# sfp-breakout.net
KiCad netlist of a schematic drawn in EAGLE
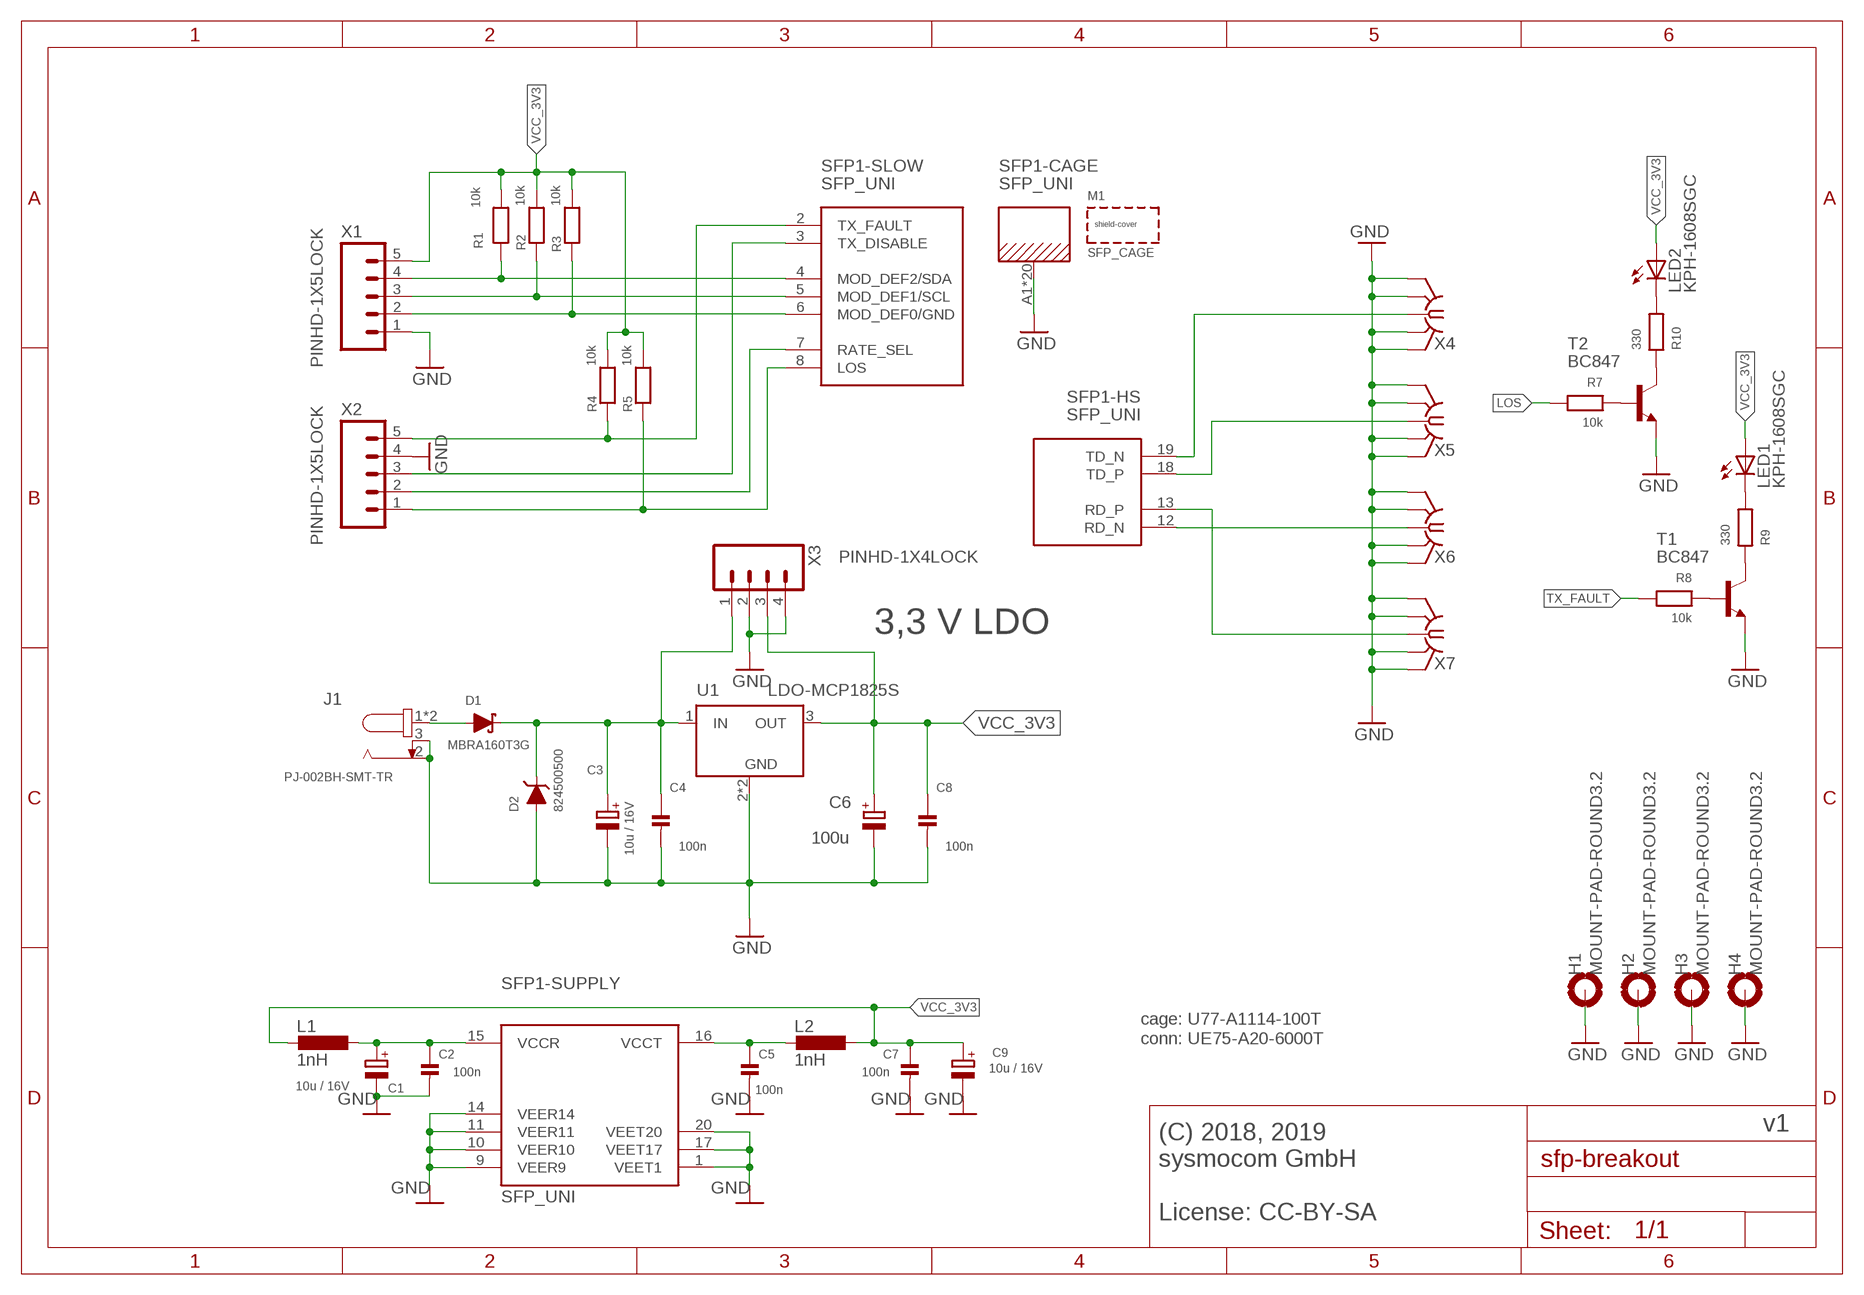
[diagram p0: schematic, sheet 1]

(export (version "E")
  (design (tool "Eeschema 10.0.6"))
  (components
    (comp (ref "C1")
      (value "10u / 16V")
      (footprint "eagle-import:CPOL1206")
      (description "CAP CER 10UF 16V X5R 1206")
      (fields
        (field (name "MANUFACTURER") "Samsung Electro-Mechanics")
        (field (name "MANUFACTURERPARTNUMBER") "CL31A106KOHNNNE")
      )
      (libsource (lib "eagle-import") (part "CPOL-EU-1206"))
    )
    (comp (ref "C2")
      (value "100n")
      (footprint "eagle-import:_0603")
      (description "CAP CER 0.1UF 16V X7R 0603")
      (fields
        (field (name "MANUFACTURER") "Samsung Electro-Mechanics")
        (field (name "MANUFACTURERPARTNUMBER") "CL10B104KO8NNNC")
      )
      (libsource (lib "eagle-import") (part "CAP_CERAMIC_0603"))
    )
    (comp (ref "C3")
      (value "10u / 16V")
      (footprint "eagle-import:CPOL1206")
      (description "CAP CER 10UF 16V X5R 1206")
      (fields
        (field (name "MANUFACTURER") "Samsung Electro-Mechanics")
        (field (name "MANUFACTURERPARTNUMBER") "CL31A106KOHNNNE")
      )
      (libsource (lib "eagle-import") (part "CPOL-EU-1206"))
    )
    (comp (ref "C4")
      (value "100n")
      (footprint "eagle-import:_0603")
      (description "CAP CER 0.1UF 16V X7R 0603")
      (fields
        (field (name "MANUFACTURER") "Samsung Electro-Mechanics")
        (field (name "MANUFACTURERPARTNUMBER") "CL10B104KO8NNNC")
      )
      (libsource (lib "eagle-import") (part "CAP_CERAMIC_0603"))
    )
    (comp (ref "C5")
      (value "100n")
      (footprint "eagle-import:_0603")
      (description "CAP CER 0.1UF 16V X7R 0603")
      (fields
        (field (name "MANUFACTURER") "Samsung Electro-Mechanics")
        (field (name "MANUFACTURERPARTNUMBER") "CL10B104KO8NNNC")
      )
      (libsource (lib "eagle-import") (part "CAP_CERAMIC_0603"))
    )
    (comp (ref "C6")
      (value "100u")
      (footprint "eagle-import:CT6032")
      (description "CAP TANT 100UF 10% 6.3V 2312")
      (fields
        (field (name "MANUFACTURER") "AVX Corporation")
        (field (name "MANUFACTURERPARTNUMBER") "TPSC107K006R0150")
      )
      (libsource (lib "eagle-import") (part "CPOL-EUCT6032"))
    )
    (comp (ref "C7")
      (value "100n")
      (footprint "eagle-import:_0603")
      (description "CAP CER 0.1UF 16V X7R 0603")
      (fields
        (field (name "MANUFACTURER") "Samsung Electro-Mechanics")
        (field (name "MANUFACTURERPARTNUMBER") "CL10B104KO8NNNC")
      )
      (libsource (lib "eagle-import") (part "CAP_CERAMIC_0603"))
    )
    (comp (ref "C8")
      (value "100n")
      (footprint "eagle-import:_0603")
      (description "CAP CER 0.1UF 16V X7R 0603")
      (fields
        (field (name "MANUFACTURER") "Samsung Electro-Mechanics")
        (field (name "MANUFACTURERPARTNUMBER") "CL10B104KO8NNNC")
      )
      (libsource (lib "eagle-import") (part "CAP_CERAMIC_0603"))
    )
    (comp (ref "C9")
      (value "10u / 16V")
      (footprint "eagle-import:CPOL1206")
      (description "CAP CER 10UF 16V X5R 1206")
      (fields
        (field (name "MANUFACTURER") "Samsung Electro-Mechanics")
        (field (name "MANUFACTURERPARTNUMBER") "CL31A106KOHNNNE")
      )
      (libsource (lib "eagle-import") (part "CPOL-EU-1206"))
    )
    (comp (ref "D1")
      (value "MBRA160T3G")
      (footprint "eagle-import:SMADIODE")
      (description "DIODE SCHOTTKY 60V 2A SMA")
      (fields
        (field (name "MANUFACTURER") "Diodes Incorporated")
        (field (name "MANUFACTURERPARTNUMBER") "B260A-13-F")
      )
      (libsource (lib "eagle-import") (part "DIODE-SCHOTTKY-SMA"))
    )
    (comp (ref "D2")
      (value "824500500")
      (footprint "eagle-import:SMADIODE")
      (description "TVS DIODE 5V 9.2V DO214AC")
      (fields (field (name "MANUFACTURER") "Würth Elektronik"))
      (libsource (lib "eagle-import") (part "DIODE-TVS-SMA"))
    )
    (comp (ref "H1")
      (value "MOUNT-PAD-ROUND3.2")
      (footprint "eagle-import:3,2-PAD")
      (description "NO DESCRIPTION")
      (fields
        (field (name "MANUFACTURER") "UNKNOWN MANUFACTURER")
        (field (name "MANUFACTURERPARTNUMBER") "UNKNOWN MANUFACTURER PART NUMBER")
      )
      (libsource (lib "eagle-import") (part "MOUNT-PAD-ROUND3.2"))
    )
    (comp (ref "H2")
      (value "MOUNT-PAD-ROUND3.2")
      (footprint "eagle-import:3,2-PAD")
      (description "NO DESCRIPTION")
      (fields
        (field (name "MANUFACTURER") "UNKNOWN MANUFACTURER")
        (field (name "MANUFACTURERPARTNUMBER") "UNKNOWN MANUFACTURER PART NUMBER")
      )
      (libsource (lib "eagle-import") (part "MOUNT-PAD-ROUND3.2"))
    )
    (comp (ref "H3")
      (value "MOUNT-PAD-ROUND3.2")
      (footprint "eagle-import:3,2-PAD")
      (description "NO DESCRIPTION")
      (fields
        (field (name "MANUFACTURER") "UNKNOWN MANUFACTURER")
        (field (name "MANUFACTURERPARTNUMBER") "UNKNOWN MANUFACTURER PART NUMBER")
      )
      (libsource (lib "eagle-import") (part "MOUNT-PAD-ROUND3.2"))
    )
    (comp (ref "H4")
      (value "MOUNT-PAD-ROUND3.2")
      (footprint "eagle-import:3,2-PAD")
      (description "NO DESCRIPTION")
      (fields
        (field (name "MANUFACTURER") "UNKNOWN MANUFACTURER")
        (field (name "MANUFACTURERPARTNUMBER") "UNKNOWN MANUFACTURER PART NUMBER")
      )
      (libsource (lib "eagle-import") (part "MOUNT-PAD-ROUND3.2"))
    )
    (comp (ref "J1")
      (value "PJ-002BH-SMT-TR")
      (footprint "eagle-import:694108106102")
      (description "CONN PWR JACK 2.5X5.5MM SOLDER")
      (fields (field (name "MANUFACTURER") "CUI Devices"))
      (libsource (lib "eagle-import") (part "694108106102"))
    )
    (comp (ref "L1")
      (value "1nH")
      (footprint "eagle-import:0603")
      (description "FIXED IND 1NH 500MA 50 MOHM SMD")
      (fields
        (field (name "MANUFACTURER") "Abracon LLC")
        (field (name "MANUFACTURERPARTNUMBER") "AIMC-0603-1N0S-T")
      )
      (libsource (lib "eagle-import") (part "L-EU_0603"))
    )
    (comp (ref "L2")
      (value "1nH")
      (footprint "eagle-import:0603")
      (description "FIXED IND 1NH 500MA 50 MOHM SMD")
      (fields
        (field (name "MANUFACTURER") "Abracon LLC")
        (field (name "MANUFACTURERPARTNUMBER") "AIMC-0603-1N0S-T")
      )
      (libsource (lib "eagle-import") (part "L-EU_0603"))
    )
    (comp (ref "LED1")
      (value "KPH-1608SGC")
      (footprint "eagle-import:CHIP-LED0603")
      (description "NO DESCRIPTION")
      (fields
        (field (name "MANUFACTURER") "UNKNOWN MANUFACTURER")
        (field (name "MANUFACTURERPARTNUMBER") "UNKNOWN MANUFACTURER PART NUMBER")
      )
      (libsource (lib "eagle-import") (part "LEDCHIP-LED0603"))
    )
    (comp (ref "LED2")
      (value "KPH-1608SGC")
      (footprint "eagle-import:CHIP-LED0603")
      (description "NO DESCRIPTION")
      (fields
        (field (name "MANUFACTURER") "UNKNOWN MANUFACTURER")
        (field (name "MANUFACTURERPARTNUMBER") "UNKNOWN MANUFACTURER PART NUMBER")
      )
      (libsource (lib "eagle-import") (part "LEDCHIP-LED0603"))
    )
    (comp (ref "R1")
      (value "10k")
      (footprint "eagle-import:_0603")
      (description "RES 10K OHM 1% 1/10W 0603")
      (fields
        (field (name "MANUFACTURER") "Stackpole Electronics Inc")
        (field (name "MANUFACTURERPARTNUMBER") "RMCF0603FT10K0")
      )
      (libsource (lib "eagle-import") (part "sfp-breakout_RESISTOR_0603"))
    )
    (comp (ref "R2")
      (value "10k")
      (footprint "eagle-import:_0603")
      (description "RES 10K OHM 1% 1/10W 0603")
      (fields
        (field (name "MANUFACTURER") "Stackpole Electronics Inc")
        (field (name "MANUFACTURERPARTNUMBER") "RMCF0603FT10K0")
      )
      (libsource (lib "eagle-import") (part "sfp-breakout_RESISTOR_0603"))
    )
    (comp (ref "R3")
      (value "10k")
      (footprint "eagle-import:_0603")
      (description "RES 10K OHM 1% 1/10W 0603")
      (fields
        (field (name "MANUFACTURER") "Stackpole Electronics Inc")
        (field (name "MANUFACTURERPARTNUMBER") "RMCF0603FT10K0")
      )
      (libsource (lib "eagle-import") (part "sfp-breakout_RESISTOR_0603"))
    )
    (comp (ref "R4")
      (value "10k")
      (footprint "eagle-import:_0603")
      (description "RES 10K OHM 1% 1/10W 0603")
      (fields
        (field (name "MANUFACTURER") "Stackpole Electronics Inc")
        (field (name "MANUFACTURERPARTNUMBER") "RMCF0603FT10K0")
      )
      (libsource (lib "eagle-import") (part "sfp-breakout_RESISTOR_0603"))
    )
    (comp (ref "R5")
      (value "10k")
      (footprint "eagle-import:_0603")
      (description "RES 10K OHM 1% 1/10W 0603")
      (fields
        (field (name "MANUFACTURER") "Stackpole Electronics Inc")
        (field (name "MANUFACTURERPARTNUMBER") "RMCF0603FT10K0")
      )
      (libsource (lib "eagle-import") (part "sfp-breakout_RESISTOR_0603"))
    )
    (comp (ref "R7")
      (value "10k")
      (footprint "eagle-import:_0603")
      (description "RES 10K OHM 1% 1/10W 0603")
      (fields
        (field (name "MANUFACTURER") "Stackpole Electronics Inc")
        (field (name "MANUFACTURERPARTNUMBER") "RMCF0603FT10K0")
      )
      (libsource (lib "eagle-import") (part "RESISTOR_0603"))
    )
    (comp (ref "R8")
      (value "10k")
      (footprint "eagle-import:_0603")
      (description "RES 10K OHM 1% 1/10W 0603")
      (fields
        (field (name "MANUFACTURER") "Stackpole Electronics Inc")
        (field (name "MANUFACTURERPARTNUMBER") "RMCF0603FT10K0")
      )
      (libsource (lib "eagle-import") (part "RESISTOR_0603"))
    )
    (comp (ref "R9")
      (value "330")
      (footprint "eagle-import:_0603")
      (description "RES SMD 330 OHM 1% 1/10W 0603")
      (fields
        (field (name "MANUFACTURER") "Yageo")
        (field (name "MANUFACTURERPARTNUMBER") "RC0603FR-07330RL")
      )
      (libsource (lib "eagle-import") (part "RESISTOR_0603"))
    )
    (comp (ref "R10")
      (value "330")
      (footprint "eagle-import:_0603")
      (description "RES SMD 330 OHM 1% 1/10W 0603")
      (fields
        (field (name "MANUFACTURER") "Yageo")
        (field (name "MANUFACTURERPARTNUMBER") "RC0603FR-07330RL")
      )
      (libsource (lib "eagle-import") (part "RESISTOR_0603"))
    )
    (comp (ref "SFP1")
      (value "SFP_UNI")
      (footprint "eagle-import:SFP_COMBINED")
      (description "CONN SFP RCPT 20POS SLD R/A SMD")
      (fields
        (field (name "CLASS") "CONNECTOR")
        (field (name "LINK") "https://www.digikey.com/product-detail/en/amphenol-icc-commercial-products/UE75-A20-6000T/UE75-A20-6000TCT-ND/1242798")
        (field (name "MANUFACTURER") "Amphenol ICC (Commercial Products)")
        (field (name "MANUFACTURERPARTNUMBER") "UE75-A20-6000T")
        (field (name "POPULATED") "TRUE")
        (field (name "ROHSCERTIFICATE") "RoHS Compliant")
        (field (name "SOURCE") "DIGIKEY")
        (field (name "SOURCEPARTNUMBER") "UE75-A20-6000TCT-ND")
      )
      (libsource (lib "eagle-import") (part "SFP_UNI"))
    )
    (comp (ref "T1")
      (value "BC847")
      (footprint "eagle-import:SOT23-BEC")
      (description "TRANS NPN 45V 0.1A SOT23")
      (fields
        (field (name "MANUFACTURER") "Nexperia USA Inc.")
        (field (name "MANUFACTURERPARTNUMBER") "BC847C,215")
      )
      (libsource (lib "eagle-import") (part "-NPN-SOT23-BECBC847C"))
    )
    (comp (ref "T2")
      (value "BC847")
      (footprint "eagle-import:SOT23-BEC")
      (description "TRANS NPN 45V 0.1A SOT23")
      (fields
        (field (name "MANUFACTURER") "Nexperia USA Inc.")
        (field (name "MANUFACTURERPARTNUMBER") "BC847C,215")
      )
      (libsource (lib "eagle-import") (part "-NPN-SOT23-BECBC847C"))
    )
    (comp (ref "U1")
      (value "LDO-MCP1825S")
      (footprint "eagle-import:SOT223")
      (description "IC REG LIN 3.3V 500MA SOT223-3")
      (fields
        (field (name "MANUFACTURER") "Microchip Technology")
        (field (name "MANUFACTURERPARTNUMBER") "MCP1825ST-3302E/DB")
      )
      (libsource (lib "eagle-import") (part "LDO-MCP1825S"))
    )
    (comp (ref "X1")
      (value "PINHD-1X5LOCK")
      (footprint "eagle-import:1X05_LOCK")
      (description "NO DESCRIPTION")
      (fields
        (field (name "MANUFACTURER") "UNKNOWN MANUFACTURER")
        (field (name "MANUFACTURERPARTNUMBER") "UNKNOWN MANUFACTURER PART NUMBER")
      )
      (libsource (lib "eagle-import") (part "PINHD-1X5LOCK"))
    )
    (comp (ref "X2")
      (value "PINHD-1X5LOCK")
      (footprint "eagle-import:1X05_LOCK")
      (description "NO DESCRIPTION")
      (fields
        (field (name "MANUFACTURER") "UNKNOWN MANUFACTURER")
        (field (name "MANUFACTURERPARTNUMBER") "UNKNOWN MANUFACTURER PART NUMBER")
      )
      (libsource (lib "eagle-import") (part "PINHD-1X5LOCK"))
    )
    (comp (ref "X3")
      (value "PINHD-1X4LOCK")
      (footprint "eagle-import:1X04_LOCK")
      (description "NO DESCRIPTION")
      (fields
        (field (name "MANUFACTURER") "UNKNOWN MANUFACTURER")
        (field (name "MANUFACTURERPARTNUMBER") "UNKNOWN MANUFACTURER PART NUMBER")
      )
      (libsource (lib "eagle-import") (part "PINHD-1X4LOCK"))
    )
    (comp (ref "X4")
      (value "SMA-F-S-EDGE")
      (footprint "eagle-import:SMA-F-S-EDGE")
      (description "NO DESCRIPTION")
      (fields
        (field (name "MANUFACTURER") "UNKNOWN MANUFACTURER")
        (field (name "MANUFACTURERPARTNUMBER") "UNKNOWN MANUFACTURER PART NUMBER")
      )
      (libsource (lib "eagle-import") (part "SMA-F-S-EDGE"))
    )
    (comp (ref "X5")
      (value "SMA-F-S-EDGE")
      (footprint "eagle-import:SMA-F-S-EDGE")
      (description "NO DESCRIPTION")
      (fields
        (field (name "MANUFACTURER") "UNKNOWN MANUFACTURER")
        (field (name "MANUFACTURERPARTNUMBER") "UNKNOWN MANUFACTURER PART NUMBER")
      )
      (libsource (lib "eagle-import") (part "SMA-F-S-EDGE"))
    )
    (comp (ref "X6")
      (value "SMA-F-S-EDGE")
      (footprint "eagle-import:SMA-F-S-EDGE")
      (description "NO DESCRIPTION")
      (fields
        (field (name "MANUFACTURER") "UNKNOWN MANUFACTURER")
        (field (name "MANUFACTURERPARTNUMBER") "UNKNOWN MANUFACTURER PART NUMBER")
      )
      (libsource (lib "eagle-import") (part "SMA-F-S-EDGE"))
    )
    (comp (ref "X7")
      (value "SMA-F-S-EDGE")
      (footprint "eagle-import:SMA-F-S-EDGE")
      (description "NO DESCRIPTION")
      (fields
        (field (name "MANUFACTURER") "UNKNOWN MANUFACTURER")
        (field (name "MANUFACTURERPARTNUMBER") "UNKNOWN MANUFACTURER PART NUMBER")
      )
      (libsource (lib "eagle-import") (part "SMA-F-S-EDGE"))
    )
  )
  (nets
    (net (code "1") (name "GND") (class "Default")
      (node (ref "C1") (pin "-") (pinfunction "-_-") (pintype "passive"))
      (node (ref "C2") (pin "2") (pinfunction "2_2") (pintype "passive"))
      (node (ref "C3") (pin "-") (pinfunction "-_-") (pintype "passive"))
      (node (ref "C4") (pin "2") (pinfunction "2_2") (pintype "passive"))
      (node (ref "C5") (pin "2") (pinfunction "2_2") (pintype "passive"))
      (node (ref "C6") (pin "-") (pinfunction "-_-") (pintype "passive"))
      (node (ref "C7") (pin "2") (pinfunction "2_2") (pintype "passive"))
      (node (ref "C8") (pin "2") (pinfunction "2_2") (pintype "passive"))
      (node (ref "C9") (pin "-") (pinfunction "-_-") (pintype "passive"))
      (node (ref "D2") (pin "A") (pinfunction "A_A") (pintype "passive"))
      (node (ref "H1") (pin "B3,2") (pinfunction "MOUNT_B3,2") (pintype "passive"))
      (node (ref "H2") (pin "B3,2") (pinfunction "MOUNT_B3,2") (pintype "passive"))
      (node (ref "H3") (pin "B3,2") (pinfunction "MOUNT_B3,2") (pintype "passive"))
      (node (ref "H4") (pin "B3,2") (pinfunction "MOUNT_B3,2") (pintype "passive"))
      (node (ref "J1") (pin "2") (pinfunction "2_2") (pintype "passive"))
      (node (ref "J1") (pin "3") (pinfunction "3_3") (pintype "passive"))
      (node (ref "SFP1") (pin "1") (pinfunction "VEET1_1") (pintype "power_in"))
      (node (ref "SFP1") (pin "10") (pinfunction "VEER10_10") (pintype "power_in"))
      (node (ref "SFP1") (pin "11") (pinfunction "VEER11_11") (pintype "power_in"))
      (node (ref "SFP1") (pin "14") (pinfunction "VEER14_14") (pintype "power_in"))
      (node (ref "SFP1") (pin "17") (pinfunction "VEET17_17") (pintype "power_in"))
      (node (ref "SFP1") (pin "20") (pinfunction "VEET20_20") (pintype "power_in"))
      (node (ref "SFP1") (pin "9") (pinfunction "VEER9_9") (pintype "power_in"))
      (node (ref "SFP1") (pin "A1") (pinfunction "CAGE_A1") (pintype "power_in"))
      (node (ref "SFP1") (pin "A10") (pinfunction "CAGE_A10") (pintype "power_in"))
      (node (ref "SFP1") (pin "A11") (pinfunction "CAGE_A11") (pintype "power_in"))
      (node (ref "SFP1") (pin "A12") (pinfunction "CAGE_A12") (pintype "power_in"))
      (node (ref "SFP1") (pin "A2") (pinfunction "CAGE_A2") (pintype "power_in"))
      (node (ref "SFP1") (pin "A3") (pinfunction "CAGE_A3") (pintype "power_in"))
      (node (ref "SFP1") (pin "A4") (pinfunction "CAGE_A4") (pintype "power_in"))
      (node (ref "SFP1") (pin "A5") (pinfunction "CAGE_A5") (pintype "power_in"))
      (node (ref "SFP1") (pin "A6") (pinfunction "CAGE_A6") (pintype "power_in"))
      (node (ref "SFP1") (pin "A7") (pinfunction "CAGE_A7") (pintype "power_in"))
      (node (ref "SFP1") (pin "A8") (pinfunction "CAGE_A8") (pintype "power_in"))
      (node (ref "SFP1") (pin "B1") (pinfunction "CAGE_B1") (pintype "power_in"))
      (node (ref "SFP1") (pin "B10") (pinfunction "CAGE_B10") (pintype "power_in"))
      (node (ref "SFP1") (pin "B2") (pinfunction "CAGE_B2") (pintype "power_in"))
      (node (ref "SFP1") (pin "B3") (pinfunction "CAGE_B3") (pintype "power_in"))
      (node (ref "SFP1") (pin "B4") (pinfunction "CAGE_B4") (pintype "power_in"))
      (node (ref "SFP1") (pin "B5") (pinfunction "CAGE_B5") (pintype "power_in"))
      (node (ref "SFP1") (pin "B6") (pinfunction "CAGE_B6") (pintype "power_in"))
      (node (ref "SFP1") (pin "B7") (pinfunction "CAGE_B7") (pintype "power_in"))
      (node (ref "SFP1") (pin "B8") (pinfunction "CAGE_B8") (pintype "power_in"))
      (node (ref "T1") (pin "E") (pinfunction "E_E") (pintype "passive"))
      (node (ref "T2") (pin "E") (pinfunction "E_E") (pintype "passive"))
      (node (ref "U1") (pin "2") (pinfunction "GND_2") (pintype "power_in"))
      (node (ref "U1") (pin "4") (pinfunction "GND_4") (pintype "power_in"))
      (node (ref "X1") (pin "1") (pinfunction "1_1") (pintype "passive"))
      (node (ref "X2") (pin "4") (pinfunction "4_4") (pintype "passive"))
      (node (ref "X3") (pin "2") (pinfunction "2_2") (pintype "passive"))
      (node (ref "X3") (pin "4") (pinfunction "4_4") (pintype "passive"))
      (node (ref "X4") (pin "BG1") (pinfunction "GND_BG1") (pintype "power_in"))
      (node (ref "X4") (pin "BG2") (pinfunction "GND_BG2") (pintype "power_in"))
      (node (ref "X4") (pin "TG1") (pinfunction "GND_TG1") (pintype "power_in"))
      (node (ref "X4") (pin "TG2") (pinfunction "GND_TG2") (pintype "power_in"))
      (node (ref "X5") (pin "BG1") (pinfunction "GND_BG1") (pintype "power_in"))
      (node (ref "X5") (pin "BG2") (pinfunction "GND_BG2") (pintype "power_in"))
      (node (ref "X5") (pin "TG1") (pinfunction "GND_TG1") (pintype "power_in"))
      (node (ref "X5") (pin "TG2") (pinfunction "GND_TG2") (pintype "power_in"))
      (node (ref "X6") (pin "BG1") (pinfunction "GND_BG1") (pintype "power_in"))
      (node (ref "X6") (pin "BG2") (pinfunction "GND_BG2") (pintype "power_in"))
      (node (ref "X6") (pin "TG1") (pinfunction "GND_TG1") (pintype "power_in"))
      (node (ref "X6") (pin "TG2") (pinfunction "GND_TG2") (pintype "power_in"))
      (node (ref "X7") (pin "BG1") (pinfunction "GND_BG1") (pintype "power_in"))
      (node (ref "X7") (pin "BG2") (pinfunction "GND_BG2") (pintype "power_in"))
      (node (ref "X7") (pin "TG1") (pinfunction "GND_TG1") (pintype "power_in"))
      (node (ref "X7") (pin "TG2") (pinfunction "GND_TG2") (pintype "power_in"))
    )
    (net (code "2") (name "LOS") (class "Default")
      (node (ref "R5") (pin "1") (pinfunction "1_1") (pintype "passive"))
      (node (ref "R7") (pin "2") (pinfunction "2_2") (pintype "passive"))
      (node (ref "SFP1") (pin "8") (pinfunction "LOS_8") (pintype "output"))
      (node (ref "X2") (pin "1") (pinfunction "1_1") (pintype "passive"))
    )
    (net (code "3") (name "Net-(D1-PadA)") (class "Default")
      (node (ref "D1") (pin "A") (pinfunction "A_A") (pintype "passive"))
      (node (ref "J1") (pin "1") (pinfunction "1_1") (pintype "passive"))
      (node (ref "J1") (pin "1-1") (pinfunction "1_1-1") (pintype "passive"))
    )
    (net (code "4") (name "Net-(LED1-PadC)") (class "Default")
      (node (ref "LED1") (pin "C") (pinfunction "C_C") (pintype "passive"))
      (node (ref "R9") (pin "2") (pinfunction "2_2") (pintype "passive"))
    )
    (net (code "5") (name "Net-(LED2-PadC)") (class "Default")
      (node (ref "LED2") (pin "C") (pinfunction "C_C") (pintype "passive"))
      (node (ref "R10") (pin "2") (pinfunction "2_2") (pintype "passive"))
    )
    (net (code "6") (name "Net-(R7-Pad1)") (class "Default")
      (node (ref "R7") (pin "1") (pinfunction "1_1") (pintype "passive"))
      (node (ref "T2") (pin "B") (pinfunction "B_B") (pintype "passive"))
    )
    (net (code "7") (name "Net-(R8-Pad1)") (class "Default")
      (node (ref "R8") (pin "1") (pinfunction "1_1") (pintype "passive"))
      (node (ref "T1") (pin "B") (pinfunction "B_B") (pintype "passive"))
    )
    (net (code "8") (name "Net-(R9-Pad1)") (class "Default")
      (node (ref "R9") (pin "1") (pinfunction "1_1") (pintype "passive"))
      (node (ref "T1") (pin "C") (pinfunction "C_C") (pintype "passive"))
    )
    (net (code "9") (name "Net-(R10-Pad1)") (class "Default")
      (node (ref "R10") (pin "1") (pinfunction "1_1") (pintype "passive"))
      (node (ref "T2") (pin "C") (pinfunction "C_C") (pintype "passive"))
    )
    (net (code "10") (name "Net-(SFP1B-RD_N)") (class "Default")
      (node (ref "SFP1") (pin "12") (pinfunction "RD_N_12") (pintype "output"))
      (node (ref "X6") (pin "C") (pinfunction "1_C") (pintype "passive"))
    )
    (net (code "11") (name "Net-(SFP1B-RD_P)") (class "Default")
      (node (ref "SFP1") (pin "13") (pinfunction "RD_P_13") (pintype "output"))
      (node (ref "X7") (pin "C") (pinfunction "1_C") (pintype "passive"))
    )
    (net (code "12") (name "Net-(SFP1B-TD_N)") (class "Default")
      (node (ref "SFP1") (pin "19") (pinfunction "TD_N_19") (pintype "input"))
      (node (ref "X4") (pin "C") (pinfunction "1_C") (pintype "passive"))
    )
    (net (code "13") (name "Net-(SFP1B-TD_P)") (class "Default")
      (node (ref "SFP1") (pin "18") (pinfunction "TD_P_18") (pintype "input"))
      (node (ref "X5") (pin "C") (pinfunction "1_C") (pintype "passive"))
    )
    (net (code "14") (name "Net-(SFP1C-MOD_DEF0{slash}GND)") (class "Default")
      (node (ref "R3") (pin "1") (pinfunction "1_1") (pintype "passive"))
      (node (ref "SFP1") (pin "6") (pinfunction "MOD_DEF0/GND_6") (pintype "passive"))
      (node (ref "X1") (pin "2") (pinfunction "2_2") (pintype "passive"))
    )
    (net (code "15") (name "Net-(SFP1C-MOD_DEF1{slash}SCL)") (class "Default")
      (node (ref "R2") (pin "1") (pinfunction "1_1") (pintype "passive"))
      (node (ref "SFP1") (pin "5") (pinfunction "MOD_DEF1/SCL_5") (pintype "bidirectional"))
      (node (ref "X1") (pin "3") (pinfunction "3_3") (pintype "passive"))
    )
    (net (code "16") (name "Net-(SFP1C-MOD_DEF2{slash}SDA)") (class "Default")
      (node (ref "R1") (pin "1") (pinfunction "1_1") (pintype "passive"))
      (node (ref "SFP1") (pin "4") (pinfunction "MOD_DEF2/SDA_4") (pintype "bidirectional"))
      (node (ref "X1") (pin "4") (pinfunction "4_4") (pintype "passive"))
    )
    (net (code "17") (name "Net-(SFP1C-RATE_SEL)") (class "Default")
      (node (ref "SFP1") (pin "7") (pinfunction "RATE_SEL_7") (pintype "input"))
      (node (ref "X2") (pin "2") (pinfunction "2_2") (pintype "passive"))
    )
    (net (code "18") (name "Net-(SFP1C-TX_DISABLE)") (class "Default")
      (node (ref "SFP1") (pin "3") (pinfunction "TX_DISABLE_3") (pintype "input"))
      (node (ref "X2") (pin "3") (pinfunction "3_3") (pintype "passive"))
    )
    (net (code "19") (name "Net-(SFP1D-VCCR)") (class "Default")
      (node (ref "C1") (pin "+") (pinfunction "+_+") (pintype "passive"))
      (node (ref "C2") (pin "1") (pinfunction "1_1") (pintype "passive"))
      (node (ref "L1") (pin "1") (pinfunction "1_1") (pintype "passive"))
      (node (ref "SFP1") (pin "15") (pinfunction "VCCR_15") (pintype "power_in"))
    )
    (net (code "20") (name "Net-(SFP1D-VCCT)") (class "Default")
      (node (ref "C5") (pin "1") (pinfunction "1_1") (pintype "passive"))
      (node (ref "L2") (pin "2") (pinfunction "2_2") (pintype "passive"))
      (node (ref "SFP1") (pin "16") (pinfunction "VCCT_16") (pintype "power_in"))
    )
    (net (code "21") (name "Net-(U1-IN)") (class "Default")
      (node (ref "C3") (pin "+") (pinfunction "+_+") (pintype "passive"))
      (node (ref "C4") (pin "1") (pinfunction "1_1") (pintype "passive"))
      (node (ref "D1") (pin "C") (pinfunction "C_C") (pintype "passive"))
      (node (ref "D2") (pin "C") (pinfunction "C_C") (pintype "passive"))
      (node (ref "U1") (pin "1") (pinfunction "IN_1") (pintype "input"))
      (node (ref "X3") (pin "1") (pinfunction "1_1") (pintype "passive"))
    )
    (net (code "22") (name "TX_FAULT") (class "Default")
      (node (ref "R4") (pin "1") (pinfunction "1_1") (pintype "passive"))
      (node (ref "R8") (pin "2") (pinfunction "2_2") (pintype "passive"))
      (node (ref "SFP1") (pin "2") (pinfunction "TX_FAULT_2") (pintype "output"))
      (node (ref "X2") (pin "5") (pinfunction "5_5") (pintype "passive"))
    )
    (net (code "23") (name "VCC_3V3") (class "Default")
      (node (ref "C6") (pin "+") (pinfunction "+_+") (pintype "passive"))
      (node (ref "C7") (pin "1") (pinfunction "1_1") (pintype "passive"))
      (node (ref "C8") (pin "1") (pinfunction "1_1") (pintype "passive"))
      (node (ref "C9") (pin "+") (pinfunction "+_+") (pintype "passive"))
      (node (ref "L1") (pin "2") (pinfunction "2_2") (pintype "passive"))
      (node (ref "L2") (pin "1") (pinfunction "1_1") (pintype "passive"))
      (node (ref "LED1") (pin "A") (pinfunction "A_A") (pintype "passive"))
      (node (ref "LED2") (pin "A") (pinfunction "A_A") (pintype "passive"))
      (node (ref "R1") (pin "2") (pinfunction "2_2") (pintype "passive"))
      (node (ref "R2") (pin "2") (pinfunction "2_2") (pintype "passive"))
      (node (ref "R3") (pin "2") (pinfunction "2_2") (pintype "passive"))
      (node (ref "R4") (pin "2") (pinfunction "2_2") (pintype "passive"))
      (node (ref "R5") (pin "2") (pinfunction "2_2") (pintype "passive"))
      (node (ref "U1") (pin "3") (pinfunction "OUT_3") (pintype "passive"))
      (node (ref "X1") (pin "5") (pinfunction "5_5") (pintype "passive"))
      (node (ref "X3") (pin "3") (pinfunction "3_3") (pintype "passive"))
    )
  )
)
